# RN2483.net
KiCad netlist of a schematic drawn in Altium Designer
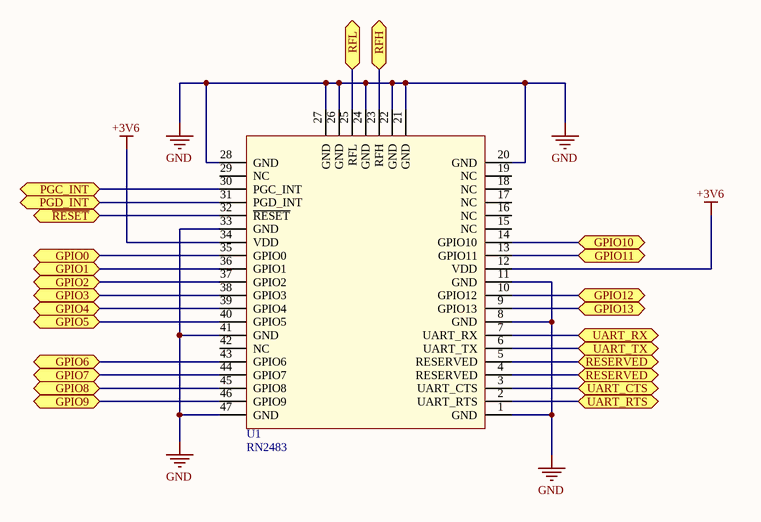
[diagram p0: RN2483.SchDoc]

(export (version "E")
  (design (tool "Eeschema 10.0.6"))
  (components
    (comp (ref "U1")
      (value "RN2483")
      (footprint "RN2483")
      (description "Low-Power Long Range LoRa® Technology  Transceiver Module")
      (libsource (lib "Kray Misc") (part "RN2483"))
    )
  )
  (nets
    (net (code "1") (name "+3V6") (class "Default")
      (node (ref "U1") (pin "12") (pinfunction "VDD_12") (pintype "passive"))
      (node (ref "U1") (pin "34") (pinfunction "VDD_34") (pintype "passive"))
    )
    (net (code "2") (name "/GPIO0") (class "Default")
      (node (ref "U1") (pin "35") (pinfunction "GPIO0_35") (pintype "passive"))
    )
    (net (code "3") (name "/GPIO1") (class "Default")
      (node (ref "U1") (pin "36") (pinfunction "GPIO1_36") (pintype "passive"))
    )
    (net (code "4") (name "/GPIO2") (class "Default")
      (node (ref "U1") (pin "37") (pinfunction "GPIO2_37") (pintype "passive"))
    )
    (net (code "5") (name "/GPIO3") (class "Default")
      (node (ref "U1") (pin "38") (pinfunction "GPIO3_38") (pintype "passive"))
    )
    (net (code "6") (name "/GPIO4") (class "Default")
      (node (ref "U1") (pin "39") (pinfunction "GPIO4_39") (pintype "passive"))
    )
    (net (code "7") (name "/GPIO5") (class "Default")
      (node (ref "U1") (pin "40") (pinfunction "GPIO5_40") (pintype "passive"))
    )
    (net (code "8") (name "/GPIO6") (class "Default")
      (node (ref "U1") (pin "43") (pinfunction "GPIO6_43") (pintype "passive"))
    )
    (net (code "9") (name "/GPIO7") (class "Default")
      (node (ref "U1") (pin "44") (pinfunction "GPIO7_44") (pintype "passive"))
    )
    (net (code "10") (name "/GPIO8") (class "Default")
      (node (ref "U1") (pin "45") (pinfunction "GPIO8_45") (pintype "passive"))
    )
    (net (code "11") (name "/GPIO9") (class "Default")
      (node (ref "U1") (pin "46") (pinfunction "GPIO9_46") (pintype "passive"))
    )
    (net (code "12") (name "/GPIO10") (class "Default")
      (node (ref "U1") (pin "14") (pinfunction "GPIO10_14") (pintype "passive"))
    )
    (net (code "13") (name "/GPIO11") (class "Default")
      (node (ref "U1") (pin "13") (pinfunction "GPIO11_13") (pintype "passive"))
    )
    (net (code "14") (name "/GPIO12") (class "Default")
      (node (ref "U1") (pin "10") (pinfunction "GPIO12_10") (pintype "passive"))
    )
    (net (code "15") (name "/GPIO13") (class "Default")
      (node (ref "U1") (pin "9") (pinfunction "GPIO13_9") (pintype "passive"))
    )
    (net (code "16") (name "/PGC_INT") (class "Default")
      (node (ref "U1") (pin "30") (pinfunction "PGC_INT_30") (pintype "passive"))
    )
    (net (code "17") (name "/PGD_INT") (class "Default")
      (node (ref "U1") (pin "31") (pinfunction "PGD_INT_31") (pintype "passive"))
    )
    (net (code "18") (name "/RESERVED") (class "Default")
      (node (ref "U1") (pin "4") (pinfunction "RESERVED_4") (pintype "passive"))
      (node (ref "U1") (pin "5") (pinfunction "RESERVED_5") (pintype "passive"))
    )
    (net (code "19") (name "/RFH") (class "Default")
      (node (ref "U1") (pin "23") (pinfunction "RFH_23") (pintype "passive"))
    )
    (net (code "20") (name "/RFL") (class "Default")
      (node (ref "U1") (pin "25") (pinfunction "RFL_25") (pintype "passive"))
    )
    (net (code "21") (name "/UART_CTS") (class "Default")
      (node (ref "U1") (pin "3") (pinfunction "UART_CTS_3") (pintype "passive"))
    )
    (net (code "22") (name "/UART_RTS") (class "Default")
      (node (ref "U1") (pin "2") (pinfunction "UART_RTS_2") (pintype "passive"))
    )
    (net (code "23") (name "/UART_RX") (class "Default")
      (node (ref "U1") (pin "7") (pinfunction "UART_RX_7") (pintype "passive"))
    )
    (net (code "24") (name "/UART_TX") (class "Default")
      (node (ref "U1") (pin "6") (pinfunction "UART_TX_6") (pintype "passive"))
    )
    (net (code "25") (name "/~{RESET}") (class "Default")
      (node (ref "U1") (pin "32") (pinfunction "~{RESET}_32") (pintype "passive"))
    )
    (net (code "26") (name "GND") (class "Default")
      (node (ref "U1") (pin "1") (pinfunction "GND_1") (pintype "passive"))
      (node (ref "U1") (pin "11") (pinfunction "GND_11") (pintype "passive"))
      (node (ref "U1") (pin "20") (pinfunction "GND_20") (pintype "passive"))
      (node (ref "U1") (pin "21") (pinfunction "GND_21") (pintype "passive"))
      (node (ref "U1") (pin "22") (pinfunction "GND_22") (pintype "passive"))
      (node (ref "U1") (pin "24") (pinfunction "GND_24") (pintype "passive"))
      (node (ref "U1") (pin "26") (pinfunction "GND_26") (pintype "passive"))
      (node (ref "U1") (pin "27") (pinfunction "GND_27") (pintype "passive"))
      (node (ref "U1") (pin "28") (pinfunction "GND_28") (pintype "passive"))
      (node (ref "U1") (pin "33") (pinfunction "GND_33") (pintype "passive"))
      (node (ref "U1") (pin "41") (pinfunction "GND_41") (pintype "passive"))
      (node (ref "U1") (pin "47") (pinfunction "GND_47") (pintype "passive"))
      (node (ref "U1") (pin "8") (pinfunction "GND_8") (pintype "passive"))
    )
    (net (code "27") (name "unconnected-(U1-NC-Pad15)") (class "Default")
      (node (ref "U1") (pin "15") (pinfunction "NC_15") (pintype "passive"))
    )
    (net (code "28") (name "unconnected-(U1-NC-Pad16)") (class "Default")
      (node (ref "U1") (pin "16") (pinfunction "NC_16") (pintype "passive"))
    )
    (net (code "29") (name "unconnected-(U1-NC-Pad17)") (class "Default")
      (node (ref "U1") (pin "17") (pinfunction "NC_17") (pintype "passive"))
    )
    (net (code "30") (name "unconnected-(U1-NC-Pad18)") (class "Default")
      (node (ref "U1") (pin "18") (pinfunction "NC_18") (pintype "passive"))
    )
    (net (code "31") (name "unconnected-(U1-NC-Pad19)") (class "Default")
      (node (ref "U1") (pin "19") (pinfunction "NC_19") (pintype "passive"))
    )
    (net (code "32") (name "unconnected-(U1-NC-Pad29)") (class "Default")
      (node (ref "U1") (pin "29") (pinfunction "NC_29") (pintype "passive"))
    )
    (net (code "33") (name "unconnected-(U1-NC-Pad42)") (class "Default")
      (node (ref "U1") (pin "42") (pinfunction "NC_42") (pintype "passive"))
    )
  )
)
